# SCH_555-Chaser_2025-11-02.net
KiCad netlist of a schematic drawn in EasyEDA
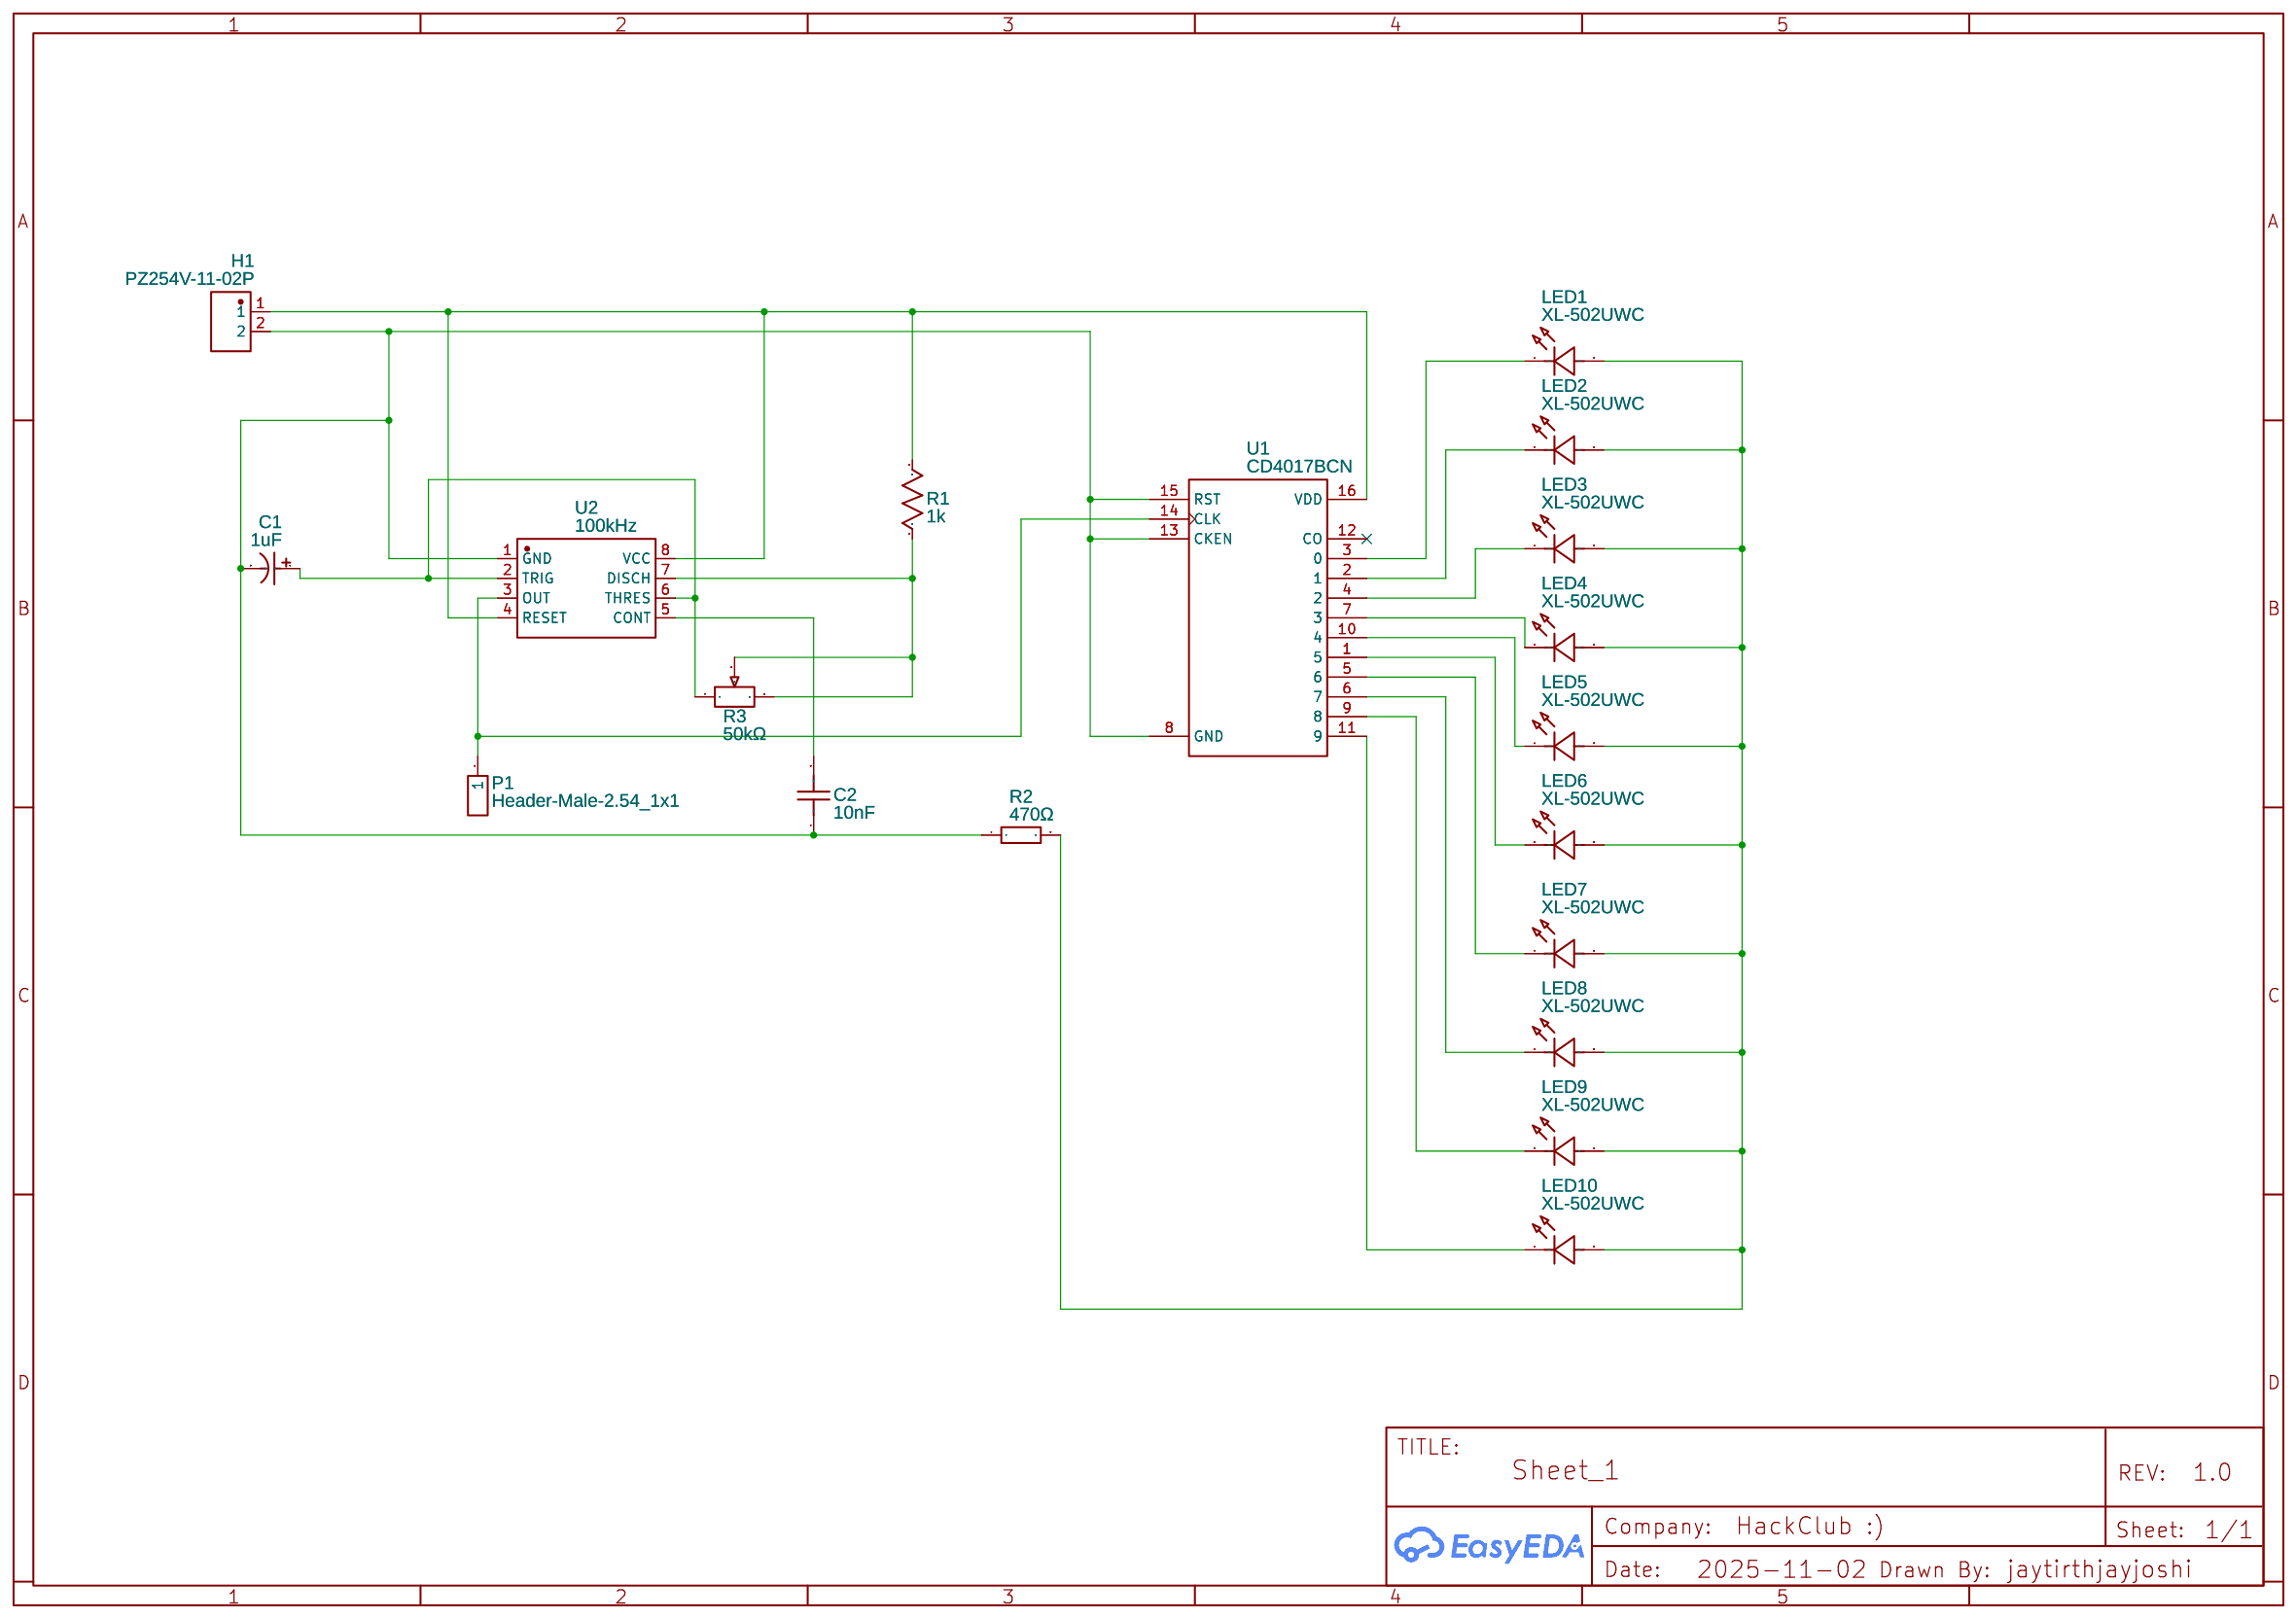
[diagram p0: schematic sheet]

(export (version "E")
  (design (tool "Eeschema 10.0.6"))
  (components
    (comp (ref "C1")
      (value "1uF")
      (fields (field (name "Manufacturer Part") "KF010M050C110A") (field (name "Manufacturer") "CapXon(丰宾)"))
      (libsource (lib "") (part "KF010M050C110A"))
    )
    (comp (ref "C2")
      (value "10nF")
      (fields (field (name "Manufacturer Part") "N09F1B103MN0B0S0N0") (field (name "Manufacturer") "STE(松田)"))
      (libsource (lib "") (part "N09F1B103MN0B0S0N0"))
    )
    (comp (ref "H1")
      (value "PZ254V-11-02P")
      (fields (field (name "Manufacturer") "XFCN(兴飞)"))
      (libsource (lib "") (part "PZ254V-11-02P"))
    )
    (comp (ref "LED1")
      (value "XL-502UWC")
      (fields (field (name "Manufacturer") "XINGLIGHT(成兴光)"))
      (libsource (lib "") (part "XL-502UWC"))
    )
    (comp (ref "LED2")
      (value "XL-502UWC")
      (fields (field (name "Manufacturer") "XINGLIGHT(成兴光)"))
      (libsource (lib "") (part "XL-502UWC"))
    )
    (comp (ref "LED3")
      (value "XL-502UWC")
      (fields (field (name "Manufacturer") "XINGLIGHT(成兴光)"))
      (libsource (lib "") (part "XL-502UWC"))
    )
    (comp (ref "LED4")
      (value "XL-502UWC")
      (fields (field (name "Manufacturer") "XINGLIGHT(成兴光)"))
      (libsource (lib "") (part "XL-502UWC"))
    )
    (comp (ref "LED5")
      (value "XL-502UWC")
      (fields (field (name "Manufacturer") "XINGLIGHT(成兴光)"))
      (libsource (lib "") (part "XL-502UWC"))
    )
    (comp (ref "LED6")
      (value "XL-502UWC")
      (fields (field (name "Manufacturer") "XINGLIGHT(成兴光)"))
      (libsource (lib "") (part "XL-502UWC"))
    )
    (comp (ref "LED7")
      (value "XL-502UWC")
      (fields (field (name "Manufacturer") "XINGLIGHT(成兴光)"))
      (libsource (lib "") (part "XL-502UWC"))
    )
    (comp (ref "LED8")
      (value "XL-502UWC")
      (fields (field (name "Manufacturer") "XINGLIGHT(成兴光)"))
      (libsource (lib "") (part "XL-502UWC"))
    )
    (comp (ref "LED9")
      (value "XL-502UWC")
      (fields (field (name "Manufacturer") "XINGLIGHT(成兴光)"))
      (libsource (lib "") (part "XL-502UWC"))
    )
    (comp (ref "LED10")
      (value "XL-502UWC")
      (fields (field (name "Manufacturer") "XINGLIGHT(成兴光)"))
      (libsource (lib "") (part "XL-502UWC"))
    )
    (comp (ref "P1")
      (value "Header-Male-2.54_1x1")
      (fields (field (name "Manufacturer Part") "2.54-1*1P针") (field (name "Manufacturer") "BOOMELE(博穆精密)"))
      (libsource (lib "") (part "Header-Male-2.54_1x1"))
    )
    (comp (ref "R1")
      (value "1k")
      (fields
        (field (name "Manufacturer Part") "MF1/4W-1KΩ±1%T52")
        (field (name "Manufacturer") "Huaxing Mechanical-Elec.")
      )
      (libsource (lib "") (part "R_AXIAL-0.3_US"))
    )
    (comp (ref "R2")
      (value "470Ω")
      (fields
        (field (name "Manufacturer Part") "MFR0W4F4700A50")
        (field (name "Manufacturer") "UNI-ROYAL(厚声)")
      )
      (libsource (lib "") (part "MFR0W4F4700A50"))
    )
    (comp (ref "R3")
      (value "50kΩ")
      (fields (field (name "Manufacturer Part") "3296X-1-503") (field (name "Manufacturer") "BOCHEN(博晨)"))
      (libsource (lib "") (part "3296X-1-503_C118912"))
    )
    (comp (ref "U1") (value "CD4017BCN") (libsource (lib "") (part "CD4017BCN")))
    (comp (ref "U2")
      (value "100kHz")
      (fields (field (name "Manufacturer Part") "NE555P") (field (name "Manufacturer") "TI(德州仪器)"))
      (libsource (lib "") (part "NE555P"))
    )
  )
  (nets
    (net (code "1") (name "Net-(LED1-A)") (class "Default")
      (node (ref "LED1") (pin "2") (pinfunction "A_2") (pintype "unspecified"))
      (node (ref "LED10") (pin "2") (pinfunction "A_2") (pintype "unspecified"))
      (node (ref "LED2") (pin "2") (pinfunction "A_2") (pintype "unspecified"))
      (node (ref "LED3") (pin "2") (pinfunction "A_2") (pintype "unspecified"))
      (node (ref "LED4") (pin "2") (pinfunction "A_2") (pintype "unspecified"))
      (node (ref "LED5") (pin "2") (pinfunction "A_2") (pintype "unspecified"))
      (node (ref "LED6") (pin "2") (pinfunction "A_2") (pintype "unspecified"))
      (node (ref "LED7") (pin "2") (pinfunction "A_2") (pintype "unspecified"))
      (node (ref "LED8") (pin "2") (pinfunction "A_2") (pintype "unspecified"))
      (node (ref "LED9") (pin "2") (pinfunction "A_2") (pintype "unspecified"))
      (node (ref "R2") (pin "2") (pinfunction "2_2") (pintype "input"))
    )
    (net (code "2") (name "Net-(LED1-K)") (class "Default")
      (node (ref "LED1") (pin "1") (pinfunction "K_1") (pintype "unspecified"))
      (node (ref "U1") (pin "3") (pinfunction "0_3") (pintype "output"))
    )
    (net (code "3") (name "Net-(LED2-K)") (class "Default")
      (node (ref "LED2") (pin "1") (pinfunction "K_1") (pintype "unspecified"))
      (node (ref "U1") (pin "2") (pinfunction "1_2") (pintype "output"))
    )
    (net (code "4") (name "Net-(LED3-K)") (class "Default")
      (node (ref "LED3") (pin "1") (pinfunction "K_1") (pintype "unspecified"))
      (node (ref "U1") (pin "4") (pinfunction "2_4") (pintype "output"))
    )
    (net (code "5") (name "Net-(LED4-K)") (class "Default")
      (node (ref "LED4") (pin "1") (pinfunction "K_1") (pintype "unspecified"))
      (node (ref "U1") (pin "7") (pinfunction "3_7") (pintype "output"))
    )
    (net (code "6") (name "Net-(LED5-K)") (class "Default")
      (node (ref "LED5") (pin "1") (pinfunction "K_1") (pintype "unspecified"))
      (node (ref "U1") (pin "10") (pinfunction "4_10") (pintype "output"))
    )
    (net (code "7") (name "Net-(LED6-K)") (class "Default")
      (node (ref "LED6") (pin "1") (pinfunction "K_1") (pintype "unspecified"))
      (node (ref "U1") (pin "1") (pinfunction "5_1") (pintype "output"))
    )
    (net (code "8") (name "Net-(LED7-K)") (class "Default")
      (node (ref "LED7") (pin "1") (pinfunction "K_1") (pintype "unspecified"))
      (node (ref "U1") (pin "5") (pinfunction "6_5") (pintype "output"))
    )
    (net (code "9") (name "Net-(LED8-K)") (class "Default")
      (node (ref "LED8") (pin "1") (pinfunction "K_1") (pintype "unspecified"))
      (node (ref "U1") (pin "6") (pinfunction "7_6") (pintype "output"))
    )
    (net (code "10") (name "Net-(LED9-K)") (class "Default")
      (node (ref "LED9") (pin "1") (pinfunction "K_1") (pintype "unspecified"))
      (node (ref "U1") (pin "9") (pinfunction "8_9") (pintype "output"))
    )
    (net (code "11") (name "Net-(LED10-K)") (class "Default")
      (node (ref "LED10") (pin "1") (pinfunction "K_1") (pintype "unspecified"))
      (node (ref "U1") (pin "11") (pinfunction "9_11") (pintype "output"))
    )
    (net (code "12") (name "Net-(U1-CKEN)") (class "Default")
      (node (ref "C1") (pin "2") (pinfunction "2_2") (pintype "input"))
      (node (ref "C2") (pin "1") (pinfunction "1_1") (pintype "unspecified"))
      (node (ref "H1") (pin "2") (pinfunction "2_2") (pintype "unspecified"))
      (node (ref "R2") (pin "1") (pinfunction "1_1") (pintype "input"))
      (node (ref "U1") (pin "13") (pinfunction "CKEN_13") (pintype "unspecified"))
      (node (ref "U1") (pin "15") (pinfunction "RST_15") (pintype "unspecified"))
      (node (ref "U1") (pin "8") (pinfunction "GND_8") (pintype "passive"))
      (node (ref "U2") (pin "1") (pinfunction "GND_1") (pintype "unspecified"))
    )
    (net (code "13") (name "Net-(U1-CLK)") (class "Default")
      (node (ref "P1") (pin "1") (pinfunction "1_1") (pintype "input"))
      (node (ref "U1") (pin "14") (pinfunction "CLK_14") (pintype "unspecified"))
      (node (ref "U2") (pin "3") (pinfunction "OUT_3") (pintype "unspecified"))
    )
    (net (code "14") (name "Net-(U1-VDD)") (class "Default")
      (node (ref "H1") (pin "1") (pinfunction "1_1") (pintype "unspecified"))
      (node (ref "R1") (pin "2") (pinfunction "2_2") (pintype "unspecified"))
      (node (ref "U1") (pin "16") (pinfunction "VDD_16") (pintype "passive"))
      (node (ref "U2") (pin "4") (pinfunction "RESET_4") (pintype "unspecified"))
      (node (ref "U2") (pin "8") (pinfunction "VCC_8") (pintype "unspecified"))
    )
    (net (code "15") (name "Net-(U2-CONT)") (class "Default")
      (node (ref "C2") (pin "2") (pinfunction "2_2") (pintype "unspecified"))
      (node (ref "U2") (pin "5") (pinfunction "CONT_5") (pintype "unspecified"))
    )
    (net (code "16") (name "Net-(U2-DISCH)") (class "Default")
      (node (ref "R1") (pin "1") (pinfunction "1_1") (pintype "unspecified"))
      (node (ref "R3") (pin "2") (pinfunction "2_2") (pintype "input"))
      (node (ref "R3") (pin "3") (pinfunction "3_3") (pintype "input"))
      (node (ref "U2") (pin "7") (pinfunction "DISCH_7") (pintype "unspecified"))
    )
    (net (code "17") (name "Net-(U2-THRES)") (class "Default")
      (node (ref "C1") (pin "1") (pinfunction "1_1") (pintype "input"))
      (node (ref "R3") (pin "1") (pinfunction "1_1") (pintype "input"))
      (node (ref "U2") (pin "2") (pinfunction "TRIG_2") (pintype "unspecified"))
      (node (ref "U2") (pin "6") (pinfunction "THRES_6") (pintype "unspecified"))
    )
    (net (code "18") (name "unconnected-(U1-CO-Pad12)") (class "Default")
      (node (ref "U1") (pin "12") (pinfunction "CO_12") (pintype "output+no_connect"))
    )
  )
)
